# F1.net
KiCad netlist of a schematic drawn in EAGLE
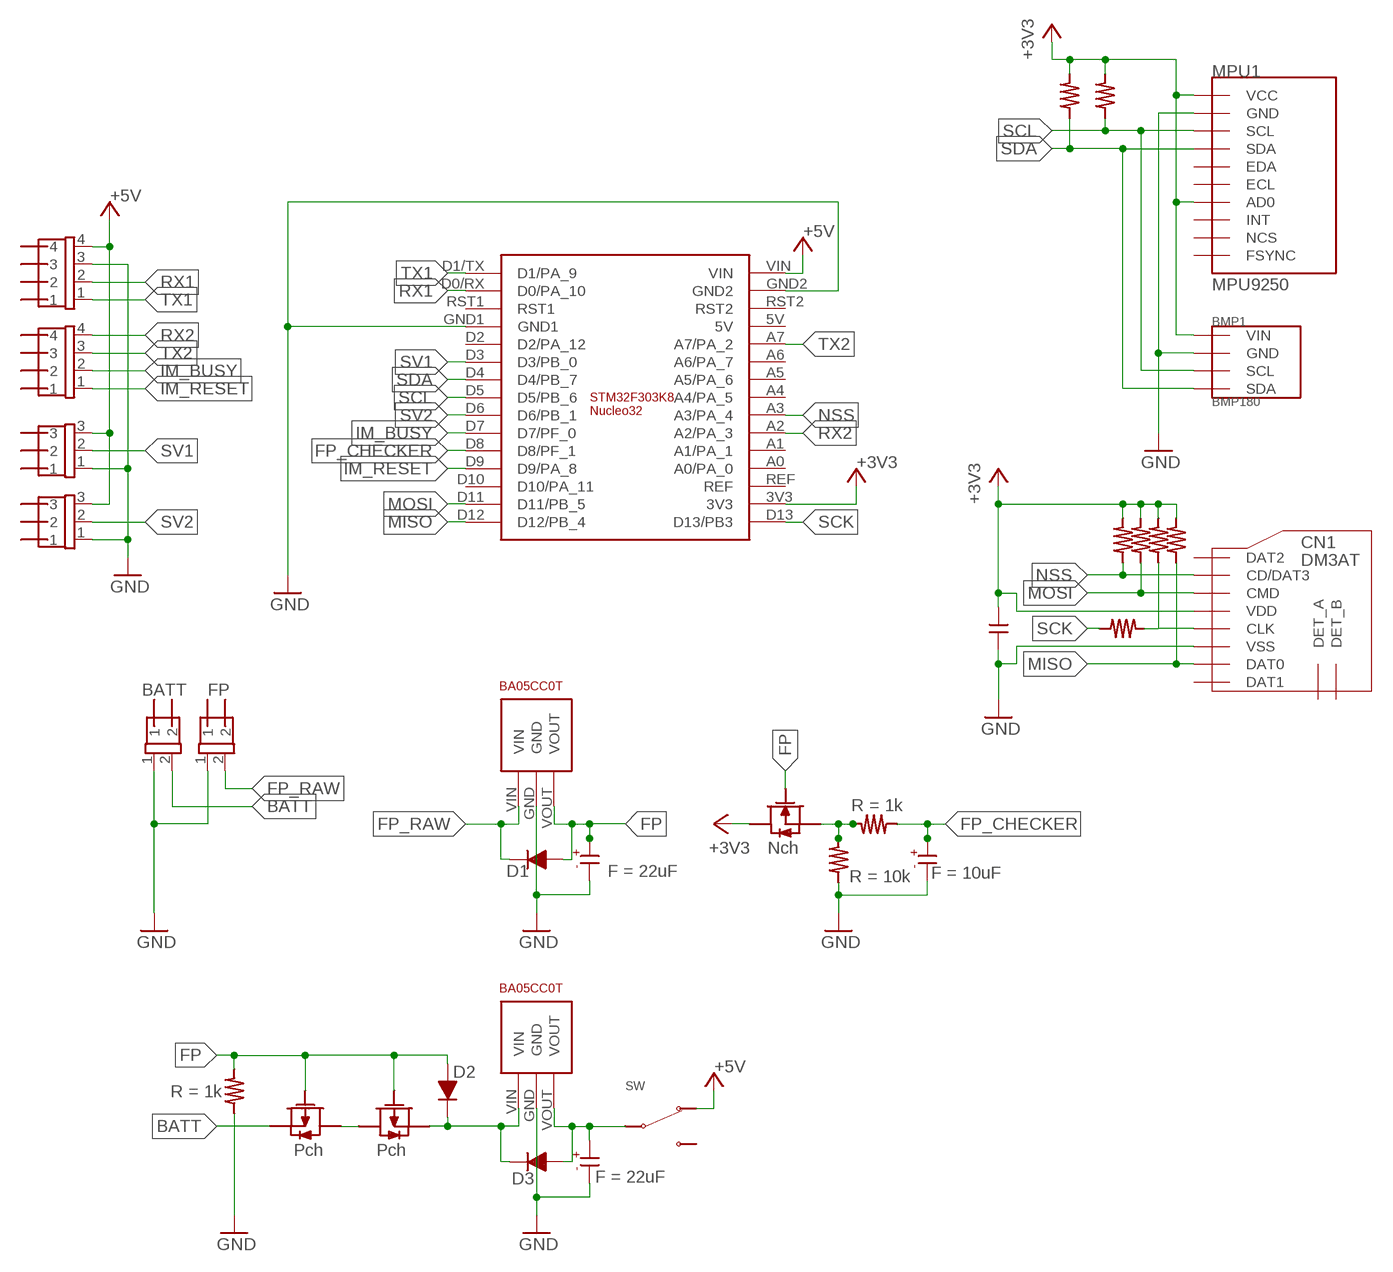
[diagram p0: schematic, sheet 1]

(export (version "E")
  (design (tool "Eeschema 10.0.6"))
  (components
    (comp (ref "BATT")
      (value "2PIN")
      (footprint "eagle-import:2PIN")
      (libsource (lib "eagle-import") (part "2PIN"))
    )
    (comp (ref "BMP1")
      (value "BMP180")
      (footprint "eagle-import:GY-68")
      (libsource (lib "eagle-import") (part "BMP180"))
    )
    (comp (ref "C1")
      (value "22uF")
      (footprint "eagle-import:CAPACITOR-ELECTROLYTIC_1")
      (fields (field (name "F") "22uF"))
      (libsource (lib "eagle-import") (part "CAPACITOR-ELECTROLYTIC_1"))
    )
    (comp (ref "C2")
      (value "CAPACITOR-ELECTROLYTIC_1")
      (footprint "eagle-import:CAPACITOR-ELECTROLYTIC_1")
      (fields (field (name "F") "22uF"))
      (libsource (lib "eagle-import") (part "CAPACITOR-ELECTROLYTIC_1"))
    )
    (comp (ref "C3")
      (value "CAPACITOR-ELECTROLYTIC_1")
      (footprint "eagle-import:CAPACITOR-ELECTROLYTIC_1")
      (fields (field (name "F") "10uF"))
      (libsource (lib "eagle-import") (part "CAPACITOR-ELECTROLYTIC_1"))
    )
    (comp (ref "C4")
      (value "CAPACITOR-CERAMICC_1")
      (footprint "eagle-import:CAPACITOR-CERAMICC_1")
      (libsource (lib "eagle-import") (part "CAPACITOR-CERAMICC_1"))
    )
    (comp (ref "CN1")
      (value "DM3AT")
      (footprint "eagle-import:DM3AT")
      (libsource (lib "eagle-import") (part "DM3AT"))
    )
    (comp (ref "CONN1")
      (value "4PIN")
      (footprint "eagle-import:4PIN")
      (libsource (lib "eagle-import") (part "4PIN"))
    )
    (comp (ref "CONN2")
      (value "4PIN")
      (footprint "eagle-import:4PIN")
      (libsource (lib "eagle-import") (part "4PIN"))
    )
    (comp (ref "CONN3")
      (value "3PIN")
      (footprint "eagle-import:3PIN")
      (libsource (lib "eagle-import") (part "3PIN"))
    )
    (comp (ref "CONN4")
      (value "3PIN")
      (footprint "eagle-import:3PIN")
      (libsource (lib "eagle-import") (part "3PIN"))
    )
    (comp (ref "CP1")
      (value "STM32F303K8-NUCLEO32")
      (footprint "eagle-import:STM32-NUCLEO32")
      (libsource (lib "eagle-import") (part "STM32F303K8-NUCLEO32"))
    )
    (comp (ref "D1")
      (value "DIODE")
      (footprint "eagle-import:DIODE")
      (libsource (lib "eagle-import") (part "DIODE"))
    )
    (comp (ref "FRIGHT-PIN")
      (value "2PIN")
      (footprint "eagle-import:2PIN")
      (libsource (lib "eagle-import") (part "2PIN"))
    )
    (comp (ref "MPU1")
      (value "MPU9250")
      (footprint "eagle-import:GY-9250")
      (libsource (lib "eagle-import") (part "MPU9250"))
    )
    (comp (ref "R1")
      (value "RESISTER")
      (footprint "eagle-import:REGISTER")
      (fields (field (name "R") "1k"))
      (libsource (lib "eagle-import") (part "RESISTER"))
    )
    (comp (ref "R2")
      (value "RESISTER")
      (footprint "eagle-import:REGISTER")
      (fields (field (name "R") "10k"))
      (libsource (lib "eagle-import") (part "RESISTER"))
    )
    (comp (ref "R3")
      (value "RESISTER")
      (footprint "eagle-import:REGISTER")
      (fields (field (name "R") "1k"))
      (libsource (lib "eagle-import") (part "RESISTER"))
    )
    (comp (ref "R4")
      (value "RESISTER")
      (footprint "eagle-import:REGISTER")
      (libsource (lib "eagle-import") (part "RESISTER"))
    )
    (comp (ref "R5")
      (value "RESISTER")
      (footprint "eagle-import:REGISTER")
      (libsource (lib "eagle-import") (part "RESISTER"))
    )
    (comp (ref "R6")
      (value "RESISTER")
      (footprint "eagle-import:REGISTER")
      (libsource (lib "eagle-import") (part "RESISTER"))
    )
    (comp (ref "R7")
      (value "RESISTER")
      (footprint "eagle-import:REGISTER")
      (libsource (lib "eagle-import") (part "RESISTER"))
    )
    (comp (ref "R8")
      (value "RESISTER")
      (footprint "eagle-import:REGISTER")
      (libsource (lib "eagle-import") (part "RESISTER"))
    )
    (comp (ref "R9")
      (value "RESISTER")
      (footprint "eagle-import:REGISTER")
      (libsource (lib "eagle-import") (part "RESISTER"))
    )
    (comp (ref "R10")
      (value "RESISTER")
      (footprint "eagle-import:REGISTER")
      (libsource (lib "eagle-import") (part "RESISTER"))
    )
    (comp (ref "REG1")
      (value "BA05CC0T")
      (footprint "eagle-import:BA05CC0T")
      (libsource (lib "eagle-import") (part "BA05CC0T"))
    )
    (comp (ref "REG2")
      (value "BA05CC0T")
      (footprint "eagle-import:BA05CC0T")
      (libsource (lib "eagle-import") (part "BA05CC0T"))
    )
    (comp (ref "SW1")
      (value "SLIDE-SW_1")
      (footprint "eagle-import:SLIDE-SW")
      (libsource (lib "eagle-import") (part "SLIDE-SW_1"))
    )
    (comp (ref "U$1")
      (value "DIODE")
      (footprint "eagle-import:DIODE")
      (libsource (lib "eagle-import") (part "DIODE"))
    )
    (comp (ref "U$2")
      (value "2SJ681-PCH")
      (footprint "eagle-import:2SJ681")
      (libsource (lib "eagle-import") (part "2SJ681-PCH"))
    )
    (comp (ref "U$3")
      (value "2SJ681-PCH")
      (footprint "eagle-import:2SJ681")
      (libsource (lib "eagle-import") (part "2SJ681-PCH"))
    )
    (comp (ref "U$4")
      (value "DIODE")
      (footprint "eagle-import:DIODE")
      (libsource (lib "eagle-import") (part "DIODE"))
    )
    (comp (ref "U$5")
      (value "2SK4017-NCH")
      (footprint "eagle-import:2SK4017")
      (libsource (lib "eagle-import") (part "2SK4017-NCH"))
    )
  )
  (nets
    (net (code "1") (name "+3V3") (class "Default")
      (node (ref "BMP1") (pin "P1") (pinfunction "VIN_P1") (pintype "bidirectional"))
      (node (ref "C4") (pin "2") (pinfunction "2_2") (pintype "bidirectional"))
      (node (ref "CN1") (pin "VDD") (pinfunction "VDD_VDD") (pintype "bidirectional"))
      (node (ref "CP1") (pin "3V3") (pinfunction "3V3_3V3") (pintype "bidirectional"))
      (node (ref "MPU1") (pin "P1") (pinfunction "VCC_P1") (pintype "bidirectional"))
      (node (ref "MPU1") (pin "P7") (pinfunction "AD0_P7") (pintype "bidirectional"))
      (node (ref "R4") (pin "B") (pinfunction "B_B") (pintype "bidirectional"))
      (node (ref "R5") (pin "B") (pinfunction "B_B") (pintype "bidirectional"))
      (node (ref "R6") (pin "B") (pinfunction "B_B") (pintype "bidirectional"))
      (node (ref "R7") (pin "B") (pinfunction "B_B") (pintype "bidirectional"))
      (node (ref "R8") (pin "B") (pinfunction "B_B") (pintype "bidirectional"))
      (node (ref "R9") (pin "B") (pinfunction "B_B") (pintype "bidirectional"))
      (node (ref "U$5") (pin "DRAIN") (pinfunction "DRAIN_DRAIN") (pintype "bidirectional"))
    )
    (net (code "2") (name "+5V") (class "Default")
      (node (ref "CONN1") (pin "4") (pinfunction "4_4") (pintype "bidirectional"))
      (node (ref "CONN3") (pin "3") (pinfunction "3_3") (pintype "bidirectional"))
      (node (ref "CONN4") (pin "3") (pinfunction "3_3") (pintype "bidirectional"))
      (node (ref "CP1") (pin "VIN") (pinfunction "VIN_VIN") (pintype "bidirectional"))
      (node (ref "SW1") (pin "LEFT") (pinfunction "LEFT_LEFT") (pintype "bidirectional"))
    )
    (net (code "3") (name "BATT") (class "Default")
      (node (ref "BATT") (pin "2") (pinfunction "2_2") (pintype "bidirectional"))
      (node (ref "U$2") (pin "SOURCE") (pinfunction "SOURCE_SOURCE") (pintype "bidirectional"))
    )
    (net (code "4") (name "FP") (class "Default")
      (node (ref "C1") (pin "KS") (pinfunction "KS_KS") (pintype "bidirectional"))
      (node (ref "D1") (pin "A") (pinfunction "ANODE_A") (pintype "bidirectional"))
      (node (ref "R1") (pin "B") (pinfunction "B_B") (pintype "bidirectional"))
      (node (ref "REG1") (pin "VOUT") (pinfunction "VOUT_VOUT") (pintype "bidirectional"))
      (node (ref "U$1") (pin "A") (pinfunction "ANODE_A") (pintype "bidirectional"))
      (node (ref "U$2") (pin "GATE") (pinfunction "GATE_GATE") (pintype "bidirectional"))
      (node (ref "U$3") (pin "GATE") (pinfunction "GATE_GATE") (pintype "bidirectional"))
      (node (ref "U$5") (pin "GATE") (pinfunction "GATE_GATE") (pintype "bidirectional"))
    )
    (net (code "5") (name "FP_CHECKER") (class "Default")
      (node (ref "C3") (pin "KS") (pinfunction "KS_KS") (pintype "bidirectional"))
      (node (ref "CP1") (pin "D8") (pinfunction "D8/PF_1_D8") (pintype "bidirectional"))
      (node (ref "R3") (pin "A") (pinfunction "A_A") (pintype "bidirectional"))
    )
    (net (code "6") (name "FP_RAW") (class "Default")
      (node (ref "D1") (pin "K") (pinfunction "KASODE_K") (pintype "bidirectional"))
      (node (ref "FRIGHT-PIN") (pin "2") (pinfunction "2_2") (pintype "bidirectional"))
      (node (ref "REG1") (pin "VIN") (pinfunction "VIN_VIN") (pintype "bidirectional"))
    )
    (net (code "7") (name "GND") (class "Default")
      (node (ref "BATT") (pin "1") (pinfunction "1_1") (pintype "bidirectional"))
      (node (ref "BMP1") (pin "P2") (pinfunction "GND_P2") (pintype "bidirectional"))
      (node (ref "C1") (pin "AN") (pinfunction "AN_AN") (pintype "bidirectional"))
      (node (ref "C2") (pin "AN") (pinfunction "AN_AN") (pintype "bidirectional"))
      (node (ref "C3") (pin "AN") (pinfunction "AN_AN") (pintype "bidirectional"))
      (node (ref "C4") (pin "1") (pinfunction "1_1") (pintype "bidirectional"))
      (node (ref "CN1") (pin "VSS") (pinfunction "VSS_VSS") (pintype "bidirectional"))
      (node (ref "CONN1") (pin "3") (pinfunction "3_3") (pintype "bidirectional"))
      (node (ref "CONN3") (pin "1") (pinfunction "1_1") (pintype "bidirectional"))
      (node (ref "CONN4") (pin "1") (pinfunction "1_1") (pintype "bidirectional"))
      (node (ref "CP1") (pin "GND1") (pinfunction "GND1_GND1") (pintype "bidirectional"))
      (node (ref "CP1") (pin "GND2") (pinfunction "GND2_GND2") (pintype "bidirectional"))
      (node (ref "FRIGHT-PIN") (pin "1") (pinfunction "1_1") (pintype "bidirectional"))
      (node (ref "MPU1") (pin "P2") (pinfunction "GND_P2") (pintype "bidirectional"))
      (node (ref "R1") (pin "A") (pinfunction "A_A") (pintype "bidirectional"))
      (node (ref "R2") (pin "A") (pinfunction "A_A") (pintype "bidirectional"))
      (node (ref "REG1") (pin "GND") (pinfunction "GND_GND") (pintype "bidirectional"))
      (node (ref "REG2") (pin "GND") (pinfunction "GND_GND") (pintype "bidirectional"))
    )
    (net (code "8") (name "IM_BUSY") (class "Default")
      (node (ref "CONN2") (pin "2") (pinfunction "2_2") (pintype "bidirectional"))
      (node (ref "CP1") (pin "D7") (pinfunction "D7/PF_0_D7") (pintype "bidirectional"))
    )
    (net (code "9") (name "IM_RESET") (class "Default")
      (node (ref "CONN2") (pin "1") (pinfunction "1_1") (pintype "bidirectional"))
      (node (ref "CP1") (pin "D9") (pinfunction "D9/PA_8_D9") (pintype "bidirectional"))
    )
    (net (code "10") (name "MISO") (class "Default")
      (node (ref "CN1") (pin "DAT0") (pinfunction "DAT0_DAT0") (pintype "bidirectional"))
      (node (ref "CP1") (pin "D12") (pinfunction "D12/PB_4_D12") (pintype "bidirectional"))
      (node (ref "R6") (pin "A") (pinfunction "A_A") (pintype "bidirectional"))
    )
    (net (code "11") (name "MOSI") (class "Default")
      (node (ref "CN1") (pin "CMD") (pinfunction "CMD_CMD") (pintype "bidirectional"))
      (node (ref "CP1") (pin "D11") (pinfunction "D11/PB_5_D11") (pintype "bidirectional"))
      (node (ref "R8") (pin "A") (pinfunction "A_A") (pintype "bidirectional"))
    )
    (net (code "12") (name "NSS") (class "Default")
      (node (ref "CN1") (pin "CD/DAT3") (pinfunction "CD/DAT3_CD/DAT3") (pintype "bidirectional"))
      (node (ref "CP1") (pin "A3") (pinfunction "A3/PA_4_A3") (pintype "bidirectional"))
      (node (ref "R9") (pin "A") (pinfunction "A_A") (pintype "bidirectional"))
    )
    (net (code "13") (name "Net-(CN1-PadCLK)") (class "Default")
      (node (ref "CN1") (pin "CLK") (pinfunction "CLK_CLK") (pintype "bidirectional"))
      (node (ref "R10") (pin "B") (pinfunction "B_B") (pintype "bidirectional"))
      (node (ref "R7") (pin "A") (pinfunction "A_A") (pintype "bidirectional"))
    )
    (net (code "14") (name "Net-(R2-PadB)") (class "Default")
      (node (ref "R2") (pin "B") (pinfunction "B_B") (pintype "bidirectional"))
      (node (ref "R3") (pin "B") (pinfunction "B_B") (pintype "bidirectional"))
      (node (ref "U$5") (pin "SOURCE") (pinfunction "SOURCE_SOURCE") (pintype "bidirectional"))
    )
    (net (code "15") (name "Net-(U$1-KASODE)") (class "Default")
      (node (ref "REG2") (pin "VIN") (pinfunction "VIN_VIN") (pintype "bidirectional"))
      (node (ref "U$1") (pin "K") (pinfunction "KASODE_K") (pintype "bidirectional"))
      (node (ref "U$3") (pin "SOURCE") (pinfunction "SOURCE_SOURCE") (pintype "bidirectional"))
      (node (ref "U$4") (pin "K") (pinfunction "KASODE_K") (pintype "bidirectional"))
    )
    (net (code "16") (name "Net-(U$2-PadDRAIN)") (class "Default")
      (node (ref "U$2") (pin "DRAIN") (pinfunction "DRAIN_DRAIN") (pintype "bidirectional"))
      (node (ref "U$3") (pin "DRAIN") (pinfunction "DRAIN_DRAIN") (pintype "bidirectional"))
    )
    (net (code "17") (name "Net-(U$4-ANODE)") (class "Default")
      (node (ref "C2") (pin "KS") (pinfunction "KS_KS") (pintype "bidirectional"))
      (node (ref "REG2") (pin "VOUT") (pinfunction "VOUT_VOUT") (pintype "bidirectional"))
      (node (ref "SW1") (pin "CENTER") (pinfunction "CENTER_CENTER") (pintype "bidirectional"))
      (node (ref "U$4") (pin "A") (pinfunction "ANODE_A") (pintype "bidirectional"))
    )
    (net (code "18") (name "RX1") (class "Default")
      (node (ref "CONN1") (pin "2") (pinfunction "2_2") (pintype "bidirectional"))
      (node (ref "CP1") (pin "D0/RX") (pinfunction "D0/PA_10_D0/RX") (pintype "bidirectional"))
    )
    (net (code "19") (name "RX2") (class "Default")
      (node (ref "CONN2") (pin "4") (pinfunction "4_4") (pintype "bidirectional"))
      (node (ref "CP1") (pin "A2") (pinfunction "A2/PA_3_A2") (pintype "bidirectional"))
    )
    (net (code "20") (name "SCK") (class "Default")
      (node (ref "CP1") (pin "D13") (pinfunction "D13/PB3_D13") (pintype "bidirectional"))
      (node (ref "R10") (pin "A") (pinfunction "A_A") (pintype "bidirectional"))
    )
    (net (code "21") (name "SCL") (class "Default")
      (node (ref "BMP1") (pin "P3") (pinfunction "SCL_P3") (pintype "bidirectional"))
      (node (ref "CP1") (pin "D5") (pinfunction "D5/PB_6_D5") (pintype "bidirectional"))
      (node (ref "MPU1") (pin "P3") (pinfunction "SCL_P3") (pintype "bidirectional"))
      (node (ref "R4") (pin "A") (pinfunction "A_A") (pintype "bidirectional"))
    )
    (net (code "22") (name "SDA") (class "Default")
      (node (ref "BMP1") (pin "P4") (pinfunction "SDA_P4") (pintype "bidirectional"))
      (node (ref "CP1") (pin "D4") (pinfunction "D4/PB_7_D4") (pintype "bidirectional"))
      (node (ref "MPU1") (pin "P4") (pinfunction "SDA_P4") (pintype "bidirectional"))
      (node (ref "R5") (pin "A") (pinfunction "A_A") (pintype "bidirectional"))
    )
    (net (code "23") (name "SV1") (class "Default")
      (node (ref "CONN3") (pin "2") (pinfunction "2_2") (pintype "bidirectional"))
      (node (ref "CP1") (pin "D3") (pinfunction "D3/PB_0_D3") (pintype "bidirectional"))
    )
    (net (code "24") (name "SV2") (class "Default")
      (node (ref "CONN4") (pin "2") (pinfunction "2_2") (pintype "bidirectional"))
      (node (ref "CP1") (pin "D6") (pinfunction "D6/PB_1_D6") (pintype "bidirectional"))
    )
    (net (code "25") (name "TX1") (class "Default")
      (node (ref "CONN1") (pin "1") (pinfunction "1_1") (pintype "bidirectional"))
      (node (ref "CP1") (pin "D1/TX") (pinfunction "D1/PA_9_D1/TX") (pintype "bidirectional"))
    )
    (net (code "26") (name "TX2") (class "Default")
      (node (ref "CONN2") (pin "3") (pinfunction "3_3") (pintype "bidirectional"))
      (node (ref "CP1") (pin "A7") (pinfunction "A7/PA_2_A7") (pintype "bidirectional"))
    )
    (net (code "27") (name "unconnected-(CN1-PadDAT1)") (class "Default")
      (node (ref "CN1") (pin "DAT1") (pinfunction "DAT1_DAT1") (pintype "bidirectional"))
    )
    (net (code "28") (name "unconnected-(CN1-PadDAT2)") (class "Default")
      (node (ref "CN1") (pin "DAT2") (pinfunction "DAT2_DAT2") (pintype "bidirectional"))
    )
    (net (code "29") (name "unconnected-(CN1-PadDET_A)") (class "Default")
      (node (ref "CN1") (pin "DET_A") (pinfunction "DET_A_DET_A") (pintype "bidirectional"))
    )
    (net (code "30") (name "unconnected-(CN1-PadDET_B)") (class "Default")
      (node (ref "CN1") (pin "DET_B") (pinfunction "DET_B_DET_B") (pintype "bidirectional"))
    )
    (net (code "31") (name "unconnected-(CP1-A0{slash}PA_0-PadA0)") (class "Default")
      (node (ref "CP1") (pin "A0") (pinfunction "A0/PA_0_A0") (pintype "bidirectional"))
    )
    (net (code "32") (name "unconnected-(CP1-A1{slash}PA_1-PadA1)") (class "Default")
      (node (ref "CP1") (pin "A1") (pinfunction "A1/PA_1_A1") (pintype "bidirectional"))
    )
    (net (code "33") (name "unconnected-(CP1-A4{slash}PA_5-PadA4)") (class "Default")
      (node (ref "CP1") (pin "A4") (pinfunction "A4/PA_5_A4") (pintype "bidirectional"))
    )
    (net (code "34") (name "unconnected-(CP1-A5{slash}PA_6-PadA5)") (class "Default")
      (node (ref "CP1") (pin "A5") (pinfunction "A5/PA_6_A5") (pintype "bidirectional"))
    )
    (net (code "35") (name "unconnected-(CP1-A6{slash}PA_7-PadA6)") (class "Default")
      (node (ref "CP1") (pin "A6") (pinfunction "A6/PA_7_A6") (pintype "bidirectional"))
    )
    (net (code "36") (name "unconnected-(CP1-D2{slash}PA_12-PadD2)") (class "Default")
      (node (ref "CP1") (pin "D2") (pinfunction "D2/PA_12_D2") (pintype "bidirectional"))
    )
    (net (code "37") (name "unconnected-(CP1-D10{slash}PA_11-PadD10)") (class "Default")
      (node (ref "CP1") (pin "D10") (pinfunction "D10/PA_11_D10") (pintype "bidirectional"))
    )
    (net (code "38") (name "unconnected-(CP1-Pad5V)") (class "Default")
      (node (ref "CP1") (pin "5V") (pinfunction "5V_5V") (pintype "bidirectional"))
    )
    (net (code "39") (name "unconnected-(CP1-PadREF)") (class "Default")
      (node (ref "CP1") (pin "REF") (pinfunction "REF_REF") (pintype "bidirectional"))
    )
    (net (code "40") (name "unconnected-(CP1-PadRST1)") (class "Default")
      (node (ref "CP1") (pin "RST1") (pinfunction "RST1_RST1") (pintype "bidirectional"))
    )
    (net (code "41") (name "unconnected-(CP1-PadRST2)") (class "Default")
      (node (ref "CP1") (pin "RST2") (pinfunction "RST2_RST2") (pintype "bidirectional"))
    )
    (net (code "42") (name "unconnected-(MPU1-ECL-PadP6)") (class "Default")
      (node (ref "MPU1") (pin "P6") (pinfunction "ECL_P6") (pintype "bidirectional"))
    )
    (net (code "43") (name "unconnected-(MPU1-EDA-PadP5)") (class "Default")
      (node (ref "MPU1") (pin "P5") (pinfunction "EDA_P5") (pintype "bidirectional"))
    )
    (net (code "44") (name "unconnected-(MPU1-FSYNC-PadP10)") (class "Default")
      (node (ref "MPU1") (pin "P10") (pinfunction "FSYNC_P10") (pintype "bidirectional"))
    )
    (net (code "45") (name "unconnected-(MPU1-INT-PadP8)") (class "Default")
      (node (ref "MPU1") (pin "P8") (pinfunction "INT_P8") (pintype "bidirectional"))
    )
    (net (code "46") (name "unconnected-(MPU1-NCS-PadP9)") (class "Default")
      (node (ref "MPU1") (pin "P9") (pinfunction "NCS_P9") (pintype "bidirectional"))
    )
    (net (code "47") (name "unconnected-(SW1-PadRIGHT)") (class "Default")
      (node (ref "SW1") (pin "RIGHT") (pinfunction "RIGHT_RIGHT") (pintype "bidirectional"))
    )
  )
)
